# ESP_SCH_2_IMU.net
KiCad netlist of a schematic drawn in EasyEDA
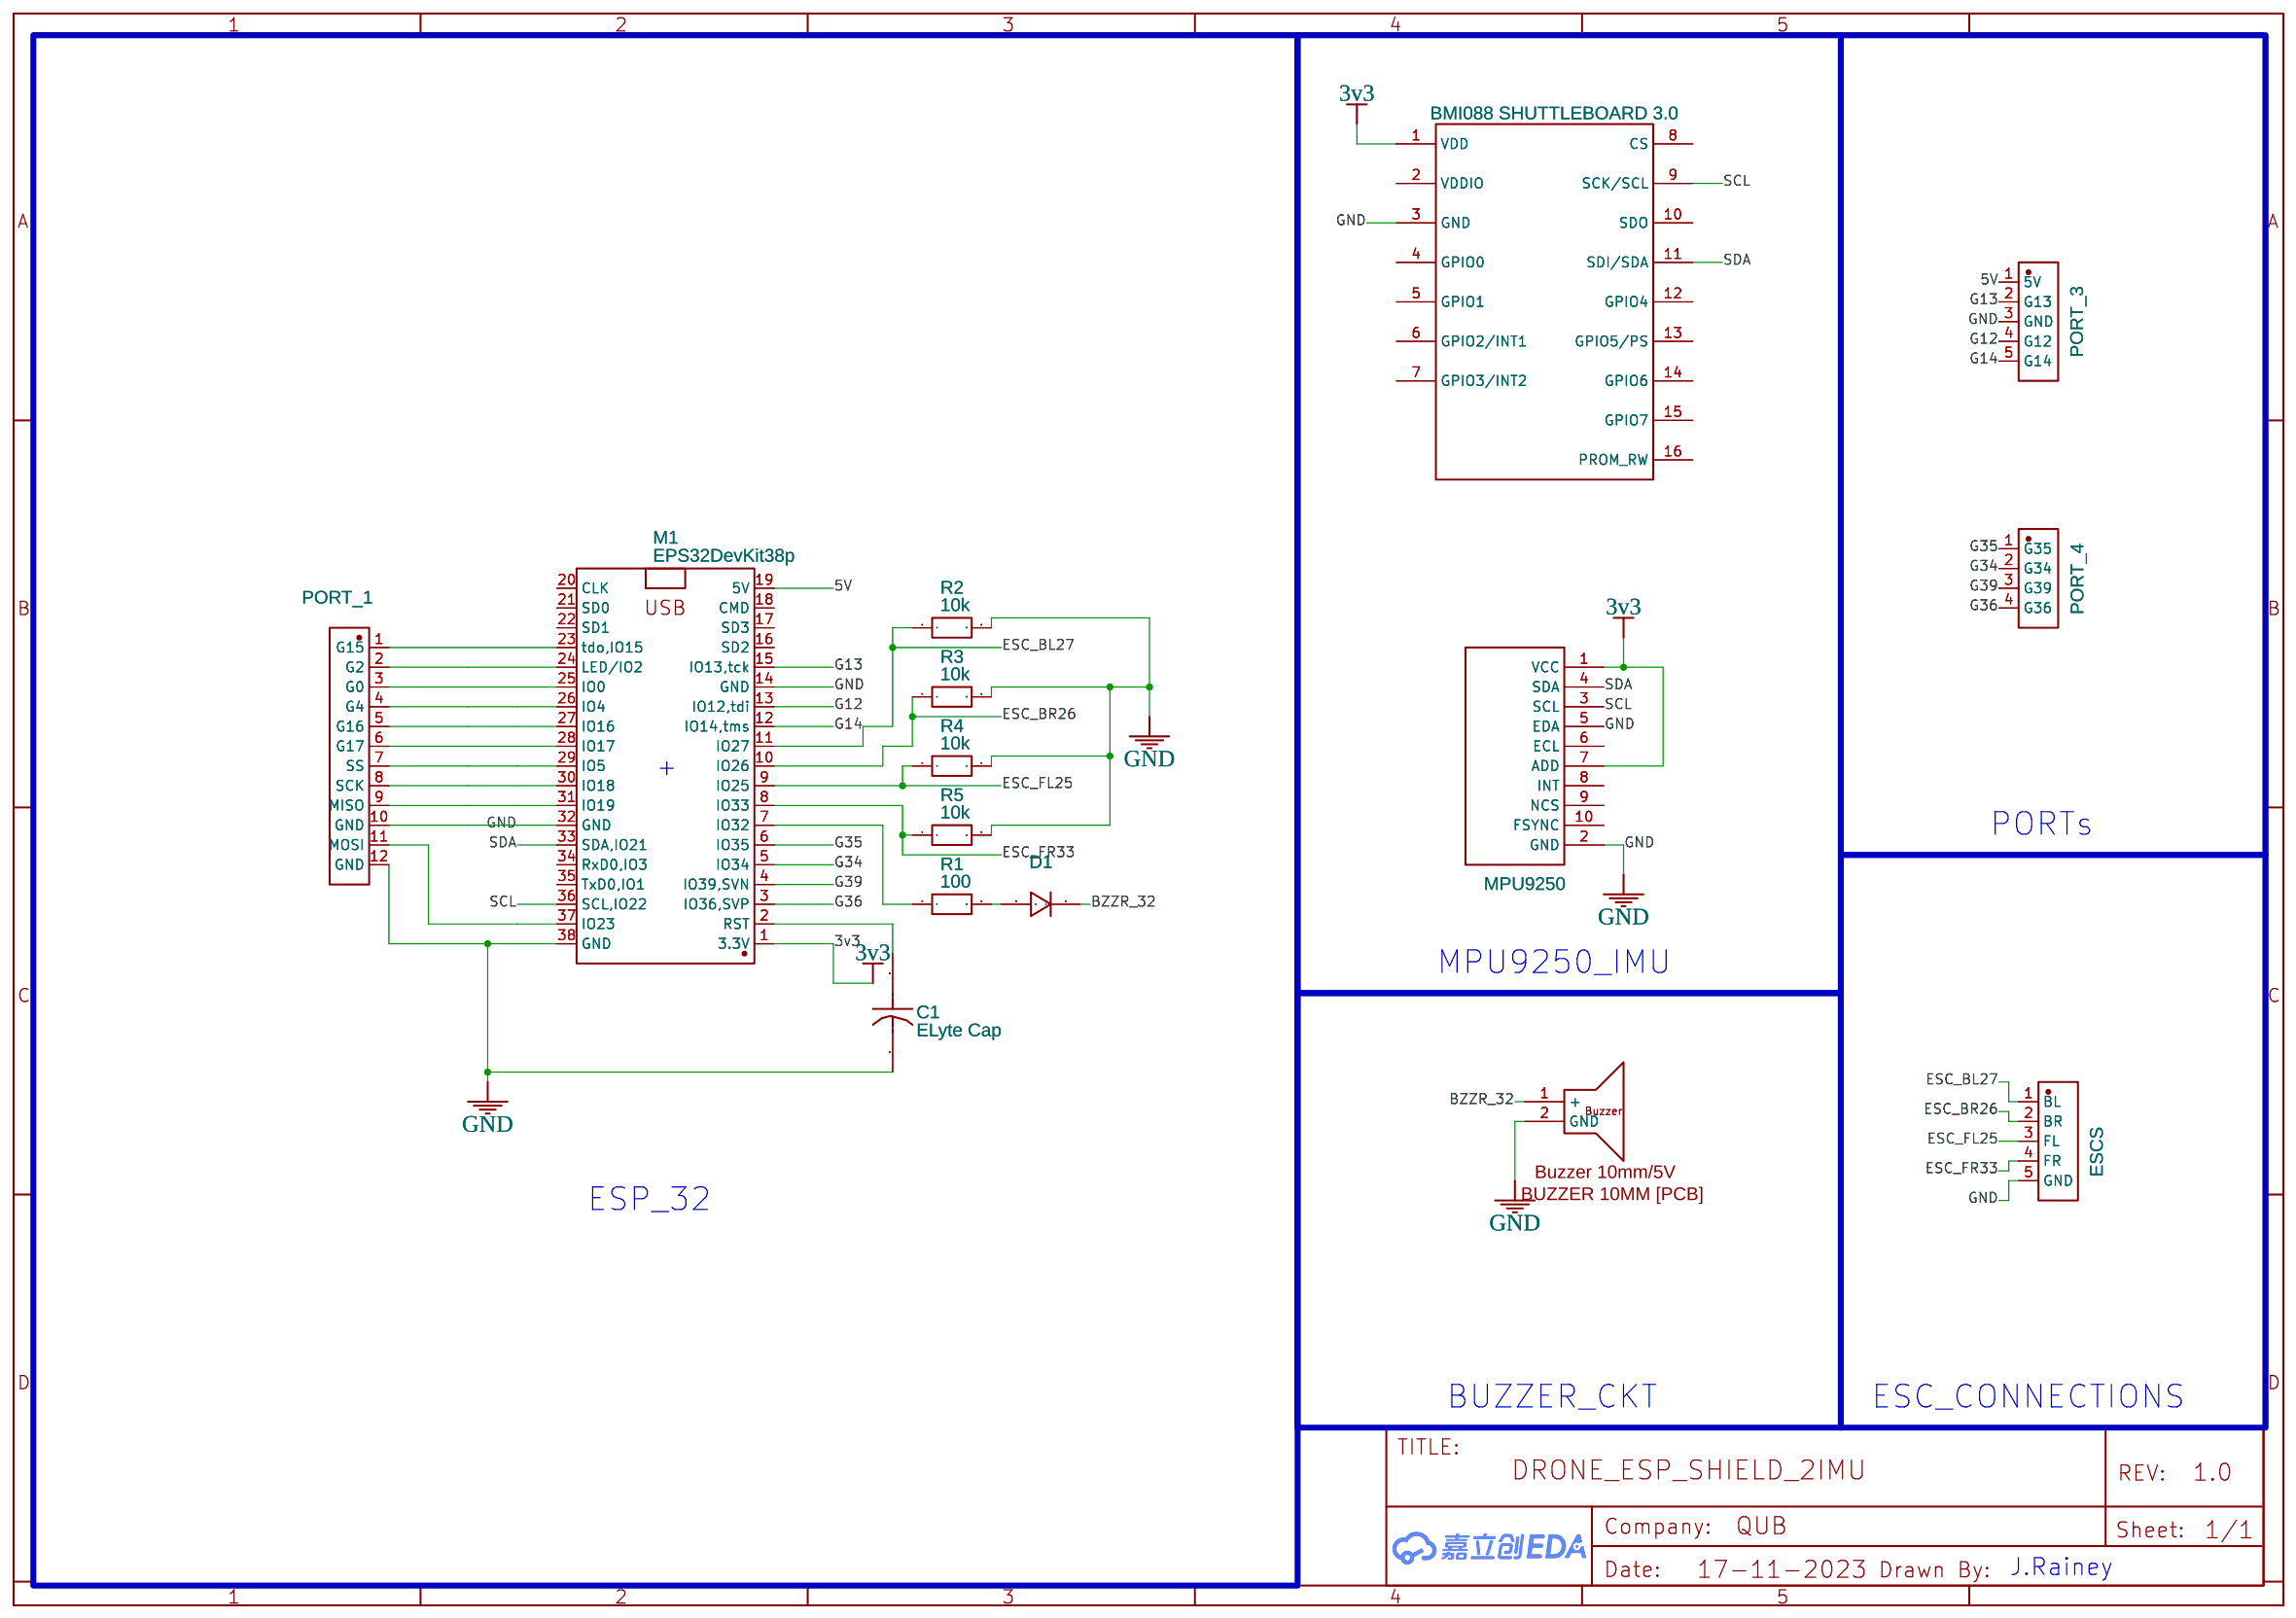
[diagram p0: schematic sheet]

(export (version "E")
  (design (tool "Eeschema 10.0.6"))
  (components
    (comp (ref "BUZZER")
      (value "Buzzer 10mm/5V")
      (fields (field (name "BOM_Manufacturer Part") "BUZZER"))
      (libsource (lib "") (part "Buzzer 10mm/5V"))
    )
    (comp (ref "C1") (value "ELyte Cap") (libsource (lib "") (part "Electrolitic Capacitor")))
    (comp (ref "D1")
      (value "1N4448")
      (fields (field (name "Manufacturer") "ST(先科)"))
      (libsource (lib "") (part "1N4448"))
    )
    (comp (ref "ESCS")
      (value "PORT_3")
      (fields (field (name "Manufacturer Part") "DS1002-03-1x5131") (field (name "Manufacturer") "CONNFLY"))
      (libsource (lib "") (part "DS1002-03-1X5131_1"))
    )
    (comp (ref "M1") (value "EPS32DevKit38p") (libsource (lib "") (part "EPS32DevKit38p")))
    (comp (ref "MPU9250") (value "MPU9250") (libsource (lib "") (part "MPU9250 MODULE")))
    (comp (ref "PORT_1")
      (value "ZX-PM2.54-1-12PY")
      (fields (field (name "Manufacturer") "Megastar(兆星)"))
      (libsource (lib "") (part "ZX-PM2.54-1-12PY"))
    )
    (comp (ref "PORT_3")
      (value "PORT_3")
      (fields (field (name "Manufacturer Part") "DS1002-03-1x5131") (field (name "Manufacturer") "CONNFLY"))
      (libsource (lib "") (part "DS1002-03-1X5131"))
    )
    (comp (ref "PORT_4")
      (value "0022285044")
      (fields (field (name "BOM_Supplier Part") "C9900016049"))
      (libsource (lib "") (part "0022285044"))
    )
    (comp (ref "R1") (value "100") (libsource (lib "") (part "R_AXIAL-0.4_EU")))
    (comp (ref "R2") (value "10k") (libsource (lib "") (part "R_AXIAL-0.4_EU")))
    (comp (ref "R3") (value "10k") (libsource (lib "") (part "R_AXIAL-0.4_EU")))
    (comp (ref "R4") (value "10k") (libsource (lib "") (part "R_AXIAL-0.4_EU")))
    (comp (ref "R5") (value "10k") (libsource (lib "") (part "R_AXIAL-0.4_EU")))
    (comp (ref "U1")
      (value "BMI088 SHUTTLEBOARD 3.0")
      (fields
        (field (name "BOM_Manufacturer Part") "BHI260AP Shuttle Board 3.0")
        (field (name "BOM_Supplier Part") "262-SB3.0BHI260AP")
      )
      (libsource (lib "") (part "BMI088 SHUTTLEBOARD 3.0"))
    )
  )
  (nets
    (net (code "1") (name "/5V") (class "Default")
      (node (ref "M1") (pin "19") (pinfunction "5V_19") (pintype "unspecified"))
      (node (ref "PORT_3") (pin "1") (pinfunction "5V_1") (pintype "unspecified"))
    )
    (net (code "2") (name "/BZZR_32") (class "Default")
      (node (ref "BUZZER") (pin "1") (pinfunction "+_1") (pintype "unspecified"))
      (node (ref "D1") (pin "2") (pinfunction "K_2") (pintype "unspecified"))
    )
    (net (code "3") (name "/ESC_BL27") (class "Default")
      (node (ref "ESCS") (pin "1") (pinfunction "BL_1") (pintype "unspecified"))
      (node (ref "M1") (pin "11") (pinfunction "IO27_11") (pintype "unspecified"))
      (node (ref "R2") (pin "1") (pinfunction "1_1") (pintype "unspecified"))
    )
    (net (code "4") (name "/ESC_BR26") (class "Default")
      (node (ref "ESCS") (pin "2") (pinfunction "BR_2") (pintype "unspecified"))
      (node (ref "M1") (pin "10") (pinfunction "IO26_10") (pintype "unspecified"))
      (node (ref "R3") (pin "1") (pinfunction "1_1") (pintype "unspecified"))
    )
    (net (code "5") (name "/ESC_FL25") (class "Default")
      (node (ref "ESCS") (pin "3") (pinfunction "FL_3") (pintype "unspecified"))
      (node (ref "M1") (pin "9") (pinfunction "IO25_9") (pintype "unspecified"))
      (node (ref "R4") (pin "1") (pinfunction "1_1") (pintype "unspecified"))
    )
    (net (code "6") (name "/ESC_FR33") (class "Default")
      (node (ref "ESCS") (pin "4") (pinfunction "FR_4") (pintype "unspecified"))
      (node (ref "M1") (pin "8") (pinfunction "IO33_8") (pintype "unspecified"))
      (node (ref "R5") (pin "1") (pinfunction "1_1") (pintype "unspecified"))
    )
    (net (code "7") (name "/G12") (class "Default")
      (node (ref "M1") (pin "13") (pinfunction "IO12,tdi_13") (pintype "unspecified"))
      (node (ref "PORT_3") (pin "4") (pinfunction "G12_4") (pintype "unspecified"))
    )
    (net (code "8") (name "/G13") (class "Default")
      (node (ref "M1") (pin "15") (pinfunction "IO13,tck_15") (pintype "unspecified"))
      (node (ref "PORT_3") (pin "2") (pinfunction "G13_2") (pintype "unspecified"))
    )
    (net (code "9") (name "/G14") (class "Default")
      (node (ref "M1") (pin "12") (pinfunction "IO14,tms_12") (pintype "unspecified"))
      (node (ref "PORT_3") (pin "5") (pinfunction "G14_5") (pintype "unspecified"))
    )
    (net (code "10") (name "/G34") (class "Default")
      (node (ref "M1") (pin "5") (pinfunction "IO34_5") (pintype "unspecified"))
      (node (ref "PORT_4") (pin "2") (pinfunction "G34_2") (pintype "unspecified"))
    )
    (net (code "11") (name "/G35") (class "Default")
      (node (ref "M1") (pin "6") (pinfunction "IO35_6") (pintype "unspecified"))
      (node (ref "PORT_4") (pin "1") (pinfunction "G35_1") (pintype "unspecified"))
    )
    (net (code "12") (name "/G36") (class "Default")
      (node (ref "M1") (pin "3") (pinfunction "IO36,SVP_3") (pintype "unspecified"))
      (node (ref "PORT_4") (pin "4") (pinfunction "G36_4") (pintype "unspecified"))
    )
    (net (code "13") (name "/G39") (class "Default")
      (node (ref "M1") (pin "4") (pinfunction "IO39,SVN_4") (pintype "unspecified"))
      (node (ref "PORT_4") (pin "3") (pinfunction "G39_3") (pintype "unspecified"))
    )
    (net (code "14") (name "/SCL") (class "Default")
      (node (ref "M1") (pin "36") (pinfunction "SCL,IO22_36") (pintype "unspecified"))
      (node (ref "MPU9250") (pin "3") (pinfunction "SCL_3") (pintype "bidirectional"))
      (node (ref "U1") (pin "9") (pinfunction "SCK/SCL_9") (pintype "unspecified"))
    )
    (net (code "15") (name "/SDA") (class "Default")
      (node (ref "M1") (pin "33") (pinfunction "SDA,IO21_33") (pintype "unspecified"))
      (node (ref "MPU9250") (pin "4") (pinfunction "SDA_4") (pintype "bidirectional"))
      (node (ref "U1") (pin "11") (pinfunction "SDI/SDA_11") (pintype "unspecified"))
    )
    (net (code "16") (name "3v3") (class "Default")
      (node (ref "M1") (pin "1") (pinfunction "3.3V_1") (pintype "unspecified"))
      (node (ref "MPU9250") (pin "1") (pinfunction "VCC_1") (pintype "passive"))
      (node (ref "MPU9250") (pin "7") (pinfunction "ADD_7") (pintype "bidirectional"))
      (node (ref "U1") (pin "1") (pinfunction "VDD_1") (pintype "unspecified"))
    )
    (net (code "17") (name "GND") (class "Default")
      (node (ref "BUZZER") (pin "2") (pinfunction "GND_2") (pintype "unspecified"))
      (node (ref "C1") (pin "2") (pinfunction "2_2") (pintype "unspecified"))
      (node (ref "ESCS") (pin "5") (pinfunction "GND_5") (pintype "unspecified"))
      (node (ref "M1") (pin "14") (pinfunction "GND_14") (pintype "unspecified"))
      (node (ref "M1") (pin "32") (pinfunction "GND_32") (pintype "unspecified"))
      (node (ref "M1") (pin "38") (pinfunction "GND_38") (pintype "unspecified"))
      (node (ref "MPU9250") (pin "2") (pinfunction "GND_2") (pintype "passive"))
      (node (ref "MPU9250") (pin "5") (pinfunction "EDA_5") (pintype "bidirectional"))
      (node (ref "PORT_1") (pin "10") (pinfunction "GND_10") (pintype "unspecified"))
      (node (ref "PORT_1") (pin "12") (pinfunction "GND_12") (pintype "unspecified"))
      (node (ref "PORT_3") (pin "3") (pinfunction "GND_3") (pintype "unspecified"))
      (node (ref "R2") (pin "2") (pinfunction "2_2") (pintype "unspecified"))
      (node (ref "R3") (pin "2") (pinfunction "2_2") (pintype "unspecified"))
      (node (ref "R4") (pin "2") (pinfunction "2_2") (pintype "unspecified"))
      (node (ref "R5") (pin "2") (pinfunction "2_2") (pintype "unspecified"))
      (node (ref "U1") (pin "3") (pinfunction "GND_3") (pintype "unspecified"))
    )
    (net (code "18") (name "Net-(D1-A)") (class "Default")
      (node (ref "D1") (pin "1") (pinfunction "A_1") (pintype "unspecified"))
      (node (ref "R1") (pin "2") (pinfunction "2_2") (pintype "unspecified"))
    )
    (net (code "19") (name "Net-(M1-IO0)") (class "Default")
      (node (ref "M1") (pin "25") (pinfunction "IO0_25") (pintype "unspecified"))
      (node (ref "PORT_1") (pin "3") (pinfunction "G0_3") (pintype "unspecified"))
    )
    (net (code "20") (name "Net-(M1-IO4)") (class "Default")
      (node (ref "M1") (pin "26") (pinfunction "IO4_26") (pintype "unspecified"))
      (node (ref "PORT_1") (pin "4") (pinfunction "G4_4") (pintype "unspecified"))
    )
    (net (code "21") (name "Net-(M1-IO5)") (class "Default")
      (node (ref "M1") (pin "29") (pinfunction "IO5_29") (pintype "unspecified"))
      (node (ref "PORT_1") (pin "7") (pinfunction "SS_7") (pintype "unspecified"))
    )
    (net (code "22") (name "Net-(M1-IO16)") (class "Default")
      (node (ref "M1") (pin "27") (pinfunction "IO16_27") (pintype "unspecified"))
      (node (ref "PORT_1") (pin "5") (pinfunction "G16_5") (pintype "unspecified"))
    )
    (net (code "23") (name "Net-(M1-IO17)") (class "Default")
      (node (ref "M1") (pin "28") (pinfunction "IO17_28") (pintype "unspecified"))
      (node (ref "PORT_1") (pin "6") (pinfunction "G17_6") (pintype "unspecified"))
    )
    (net (code "24") (name "Net-(M1-IO18)") (class "Default")
      (node (ref "M1") (pin "30") (pinfunction "IO18_30") (pintype "unspecified"))
      (node (ref "PORT_1") (pin "8") (pinfunction "SCK_8") (pintype "unspecified"))
    )
    (net (code "25") (name "Net-(M1-IO19)") (class "Default")
      (node (ref "M1") (pin "31") (pinfunction "IO19_31") (pintype "unspecified"))
      (node (ref "PORT_1") (pin "9") (pinfunction "MISO_9") (pintype "unspecified"))
    )
    (net (code "26") (name "Net-(M1-IO23)") (class "Default")
      (node (ref "M1") (pin "37") (pinfunction "IO23_37") (pintype "unspecified"))
      (node (ref "PORT_1") (pin "11") (pinfunction "MOSI_11") (pintype "unspecified"))
    )
    (net (code "27") (name "Net-(M1-IO32)") (class "Default")
      (node (ref "M1") (pin "7") (pinfunction "IO32_7") (pintype "unspecified"))
      (node (ref "R1") (pin "1") (pinfunction "1_1") (pintype "unspecified"))
    )
    (net (code "28") (name "Net-(M1-LED{slash}IO2)") (class "Default")
      (node (ref "M1") (pin "24") (pinfunction "LED/IO2_24") (pintype "unspecified"))
      (node (ref "PORT_1") (pin "2") (pinfunction "G2_2") (pintype "unspecified"))
    )
    (net (code "29") (name "Net-(M1-RST)") (class "Default")
      (node (ref "C1") (pin "1") (pinfunction "1_1") (pintype "unspecified"))
      (node (ref "M1") (pin "2") (pinfunction "RST_2") (pintype "unspecified"))
    )
    (net (code "30") (name "Net-(M1-tdo,IO15)") (class "Default")
      (node (ref "M1") (pin "23") (pinfunction "tdo,IO15_23") (pintype "unspecified"))
      (node (ref "PORT_1") (pin "1") (pinfunction "G15_1") (pintype "unspecified"))
    )
    (net (code "31") (name "unconnected-(M1-CLK-Pad20)") (class "Default")
      (node (ref "M1") (pin "20") (pinfunction "CLK_20") (pintype "unspecified"))
    )
    (net (code "32") (name "unconnected-(M1-CMD-Pad18)") (class "Default")
      (node (ref "M1") (pin "18") (pinfunction "CMD_18") (pintype "unspecified"))
    )
    (net (code "33") (name "unconnected-(M1-RxD0,IO3-Pad34)") (class "Default")
      (node (ref "M1") (pin "34") (pinfunction "RxD0,IO3_34") (pintype "unspecified"))
    )
    (net (code "34") (name "unconnected-(M1-SD0-Pad21)") (class "Default")
      (node (ref "M1") (pin "21") (pinfunction "SD0_21") (pintype "unspecified"))
    )
    (net (code "35") (name "unconnected-(M1-SD1-Pad22)") (class "Default")
      (node (ref "M1") (pin "22") (pinfunction "SD1_22") (pintype "unspecified"))
    )
    (net (code "36") (name "unconnected-(M1-SD2-Pad16)") (class "Default")
      (node (ref "M1") (pin "16") (pinfunction "SD2_16") (pintype "unspecified"))
    )
    (net (code "37") (name "unconnected-(M1-SD3-Pad17)") (class "Default")
      (node (ref "M1") (pin "17") (pinfunction "SD3_17") (pintype "unspecified"))
    )
    (net (code "38") (name "unconnected-(M1-TxD0,IO1-Pad35)") (class "Default")
      (node (ref "M1") (pin "35") (pinfunction "TxD0,IO1_35") (pintype "unspecified"))
    )
    (net (code "39") (name "unconnected-(MPU9250-ECL-Pad6)") (class "Default")
      (node (ref "MPU9250") (pin "6") (pinfunction "ECL_6") (pintype "bidirectional"))
    )
    (net (code "40") (name "unconnected-(MPU9250-FSYNC-Pad10)") (class "Default")
      (node (ref "MPU9250") (pin "10") (pinfunction "FSYNC_10") (pintype "bidirectional"))
    )
    (net (code "41") (name "unconnected-(MPU9250-INT-Pad8)") (class "Default")
      (node (ref "MPU9250") (pin "8") (pinfunction "INT_8") (pintype "bidirectional"))
    )
    (net (code "42") (name "unconnected-(MPU9250-NCS-Pad9)") (class "Default")
      (node (ref "MPU9250") (pin "9") (pinfunction "NCS_9") (pintype "bidirectional"))
    )
    (net (code "43") (name "unconnected-(U1-CS-Pad8)") (class "Default")
      (node (ref "U1") (pin "8") (pinfunction "CS_8") (pintype "unspecified"))
    )
    (net (code "44") (name "unconnected-(U1-GPIO0-Pad4)") (class "Default")
      (node (ref "U1") (pin "4") (pinfunction "GPIO0_4") (pintype "unspecified"))
    )
    (net (code "45") (name "unconnected-(U1-GPIO1-Pad5)") (class "Default")
      (node (ref "U1") (pin "5") (pinfunction "GPIO1_5") (pintype "unspecified"))
    )
    (net (code "46") (name "unconnected-(U1-GPIO2{slash}INT1-Pad6)") (class "Default")
      (node (ref "U1") (pin "6") (pinfunction "GPIO2/INT1_6") (pintype "unspecified"))
    )
    (net (code "47") (name "unconnected-(U1-GPIO3{slash}INT2-Pad7)") (class "Default")
      (node (ref "U1") (pin "7") (pinfunction "GPIO3/INT2_7") (pintype "unspecified"))
    )
    (net (code "48") (name "unconnected-(U1-GPIO4-Pad12)") (class "Default")
      (node (ref "U1") (pin "12") (pinfunction "GPIO4_12") (pintype "unspecified"))
    )
    (net (code "49") (name "unconnected-(U1-GPIO5{slash}PS-Pad13)") (class "Default")
      (node (ref "U1") (pin "13") (pinfunction "GPIO5/PS_13") (pintype "unspecified"))
    )
    (net (code "50") (name "unconnected-(U1-GPIO6-Pad14)") (class "Default")
      (node (ref "U1") (pin "14") (pinfunction "GPIO6_14") (pintype "unspecified"))
    )
    (net (code "51") (name "unconnected-(U1-GPIO7-Pad15)") (class "Default")
      (node (ref "U1") (pin "15") (pinfunction "GPIO7_15") (pintype "unspecified"))
    )
    (net (code "52") (name "unconnected-(U1-PROM_RW-Pad16)") (class "Default")
      (node (ref "U1") (pin "16") (pinfunction "PROM_RW_16") (pintype "unspecified"))
    )
    (net (code "53") (name "unconnected-(U1-SDO-Pad10)") (class "Default")
      (node (ref "U1") (pin "10") (pinfunction "SDO_10") (pintype "unspecified"))
    )
    (net (code "54") (name "unconnected-(U1-VDDIO-Pad2)") (class "Default")
      (node (ref "U1") (pin "2") (pinfunction "VDDIO_2") (pintype "unspecified"))
    )
  )
)
